# ISL6236A_DEMO.net
KiCad netlist of a schematic drawn in Altium Designer
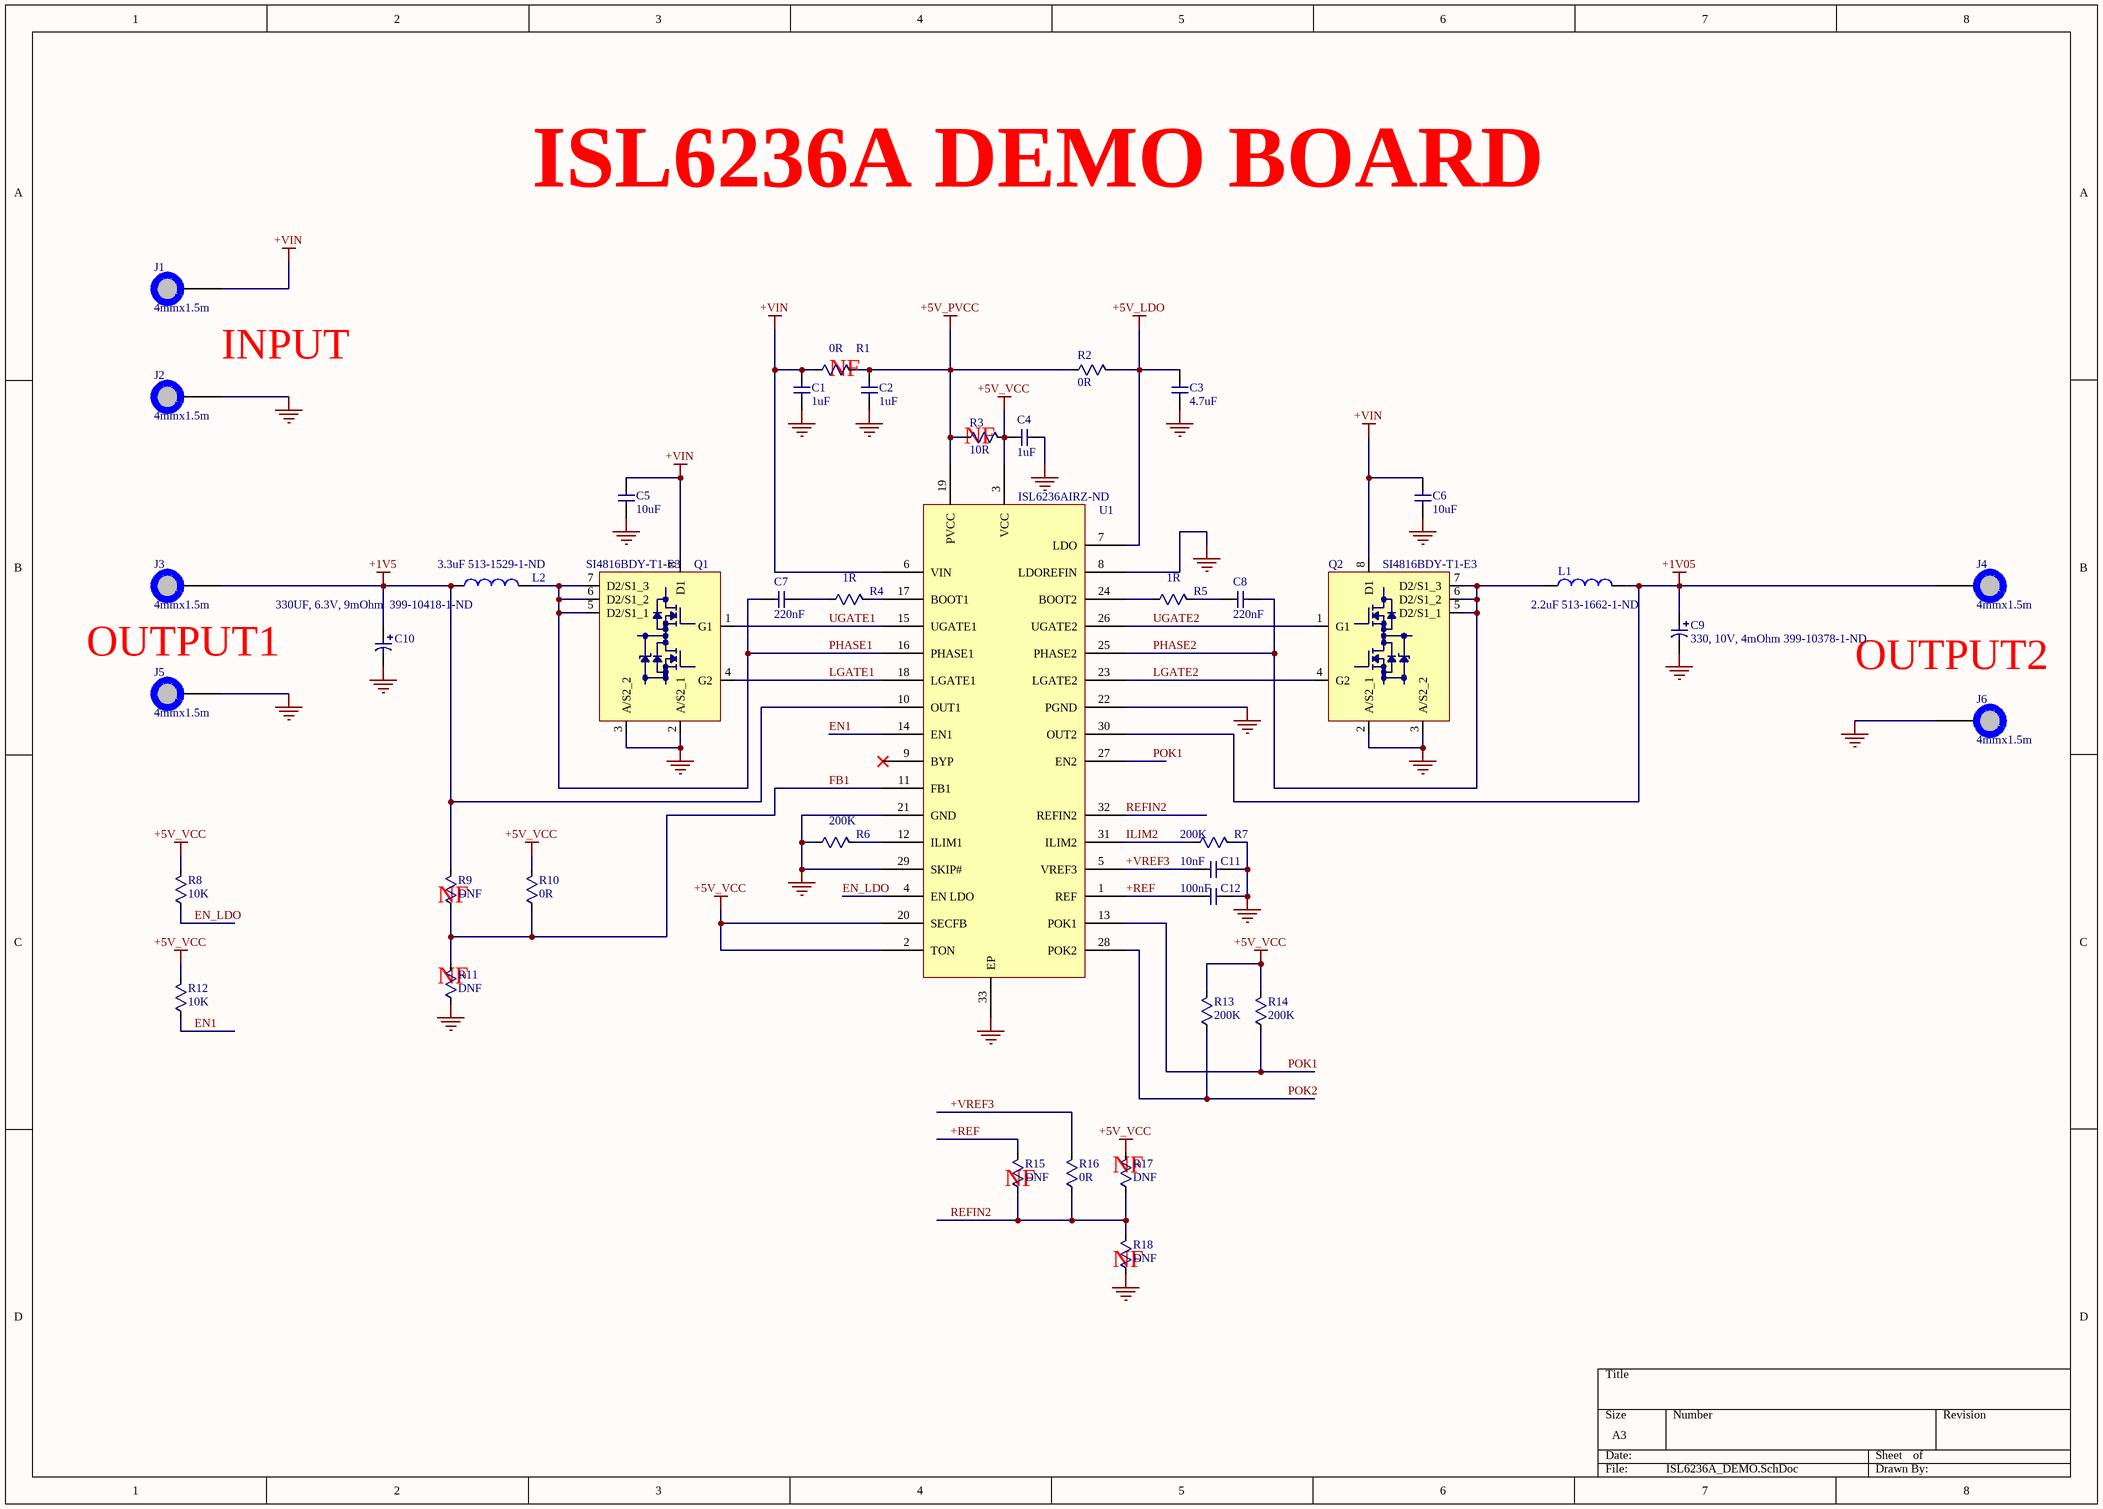
[diagram p0: ISL6236A_DEMO.SchDoc]

(export (version "E")
  (design (tool "Eeschema 10.0.6"))
  (components
    (comp (ref "C1")
      (value "1uF")
      (footprint "C0805")
      (description "CAP CER 1UF 50V 10% X7R 0805")
      (fields
        (field (name "MANUFACTURER") "Samsung Electro-Mechanics America, Inc")
        (field (name "MANUFACTURER PART NUMBER") "CL21B105KBFNNNE")
      )
      (libsource (lib "ISL6236A_DEMO_2") (part "CL21B105KBFNNNE"))
    )
    (comp (ref "C2")
      (value "1uF")
      (footprint "C0805")
      (description "CAP CER 1UF 50V 10% X7R 0805")
      (fields
        (field (name "MANUFACTURER") "Samsung Electro-Mechanics America, Inc")
        (field (name "MANUFACTURER PART NUMBER") "CL21B105KBFNNNE")
      )
      (libsource (lib "ISL6236A_DEMO_2") (part "CL21B105KBFNNNE"))
    )
    (comp (ref "C3")
      (value "4.7uF")
      (footprint "C1206")
      (description "CAP CER 4.7UF 10V 10% X5R 1206")
      (fields
        (field (name "MANUFACTURER") "Samsung Electro-Mechanics America, Inc")
        (field (name "MANUFACTURER PART NUMBER") "CL31A475KPHNNNE")
      )
      (libsource (lib "ISL6236A_DEMO_2") (part "CL31A475KPHNNNE"))
    )
    (comp (ref "C4")
      (value "1uF")
      (footprint "C0805")
      (description "CAP CER 1UF 50V 10% X7R 0805")
      (fields
        (field (name "MANUFACTURER") "Samsung Electro-Mechanics America, Inc")
        (field (name "MANUFACTURER PART NUMBER") "CL21B105KBFNNNE")
      )
      (libsource (lib "ISL6236A_DEMO_2") (part "CL21B105KBFNNNE"))
    )
    (comp (ref "C5")
      (value "10uF")
      (footprint "C1206")
      (description "CAP CER 10UF 50V Y5V 1210")
      (fields
        (field (name "MANUFACTURER") "Murata Electronics North America")
        (field (name "MANUFACTURER PART NUMBER") "GRM32DF51H106ZA01L")
      )
      (libsource (lib "ISL6236A_DEMO_2") (part "GRM32DF51H106ZA01L"))
    )
    (comp (ref "C6")
      (value "10uF")
      (footprint "C1206")
      (description "CAP CER 10UF 50V Y5V 1210")
      (fields
        (field (name "MANUFACTURER") "Murata Electronics North America")
        (field (name "MANUFACTURER PART NUMBER") "GRM32DF51H106ZA01L")
      )
      (libsource (lib "ISL6236A_DEMO_2") (part "GRM32DF51H106ZA01L"))
    )
    (comp (ref "C7")
      (value "220nF")
      (footprint "C0805")
      (description "CAP CER 0.22UF 50V 10% X7R 0805")
      (fields
        (field (name "MANUFACTURER") "Taiyo Yuden")
        (field (name "MANUFACTURER PART NUMBER") "UMK212B7224KG-T")
      )
      (libsource (lib "ISL6236A_DEMO_2") (part "UMK212B7224KG-T"))
    )
    (comp (ref "C8")
      (value "220nF")
      (footprint "C0805")
      (description "CAP CER 0.22UF 50V 10% X7R 0805")
      (fields
        (field (name "MANUFACTURER") "Taiyo Yuden")
        (field (name "MANUFACTURER PART NUMBER") "UMK212B7224KG-T")
      )
      (libsource (lib "ISL6236A_DEMO_2") (part "UMK212B7224KG-T"))
    )
    (comp (ref "C9")
      (value "330, 10V, 4mOhm 399-10378-1-ND")
      (footprint "C7343-43")
      (description "CAP TANT 330UF 10V 20% 2917")
      (fields
        (field (name "MANUFACTURER") "Kemet")
        (field (name "MANUFACTURER PART NUMBER") "T530X337M010ATE004")
      )
      (libsource (lib "ISL6236A_DEMO_2") (part "T530X337M010ATE004"))
    )
    (comp (ref "C10")
      (value "330UF, 6.3V, 9mOhm  399-10418-1-ND")
      (footprint "C7343-31")
      (description "CAP TANT 330UF 6.3V 20% 2917")
      (fields
        (field (name "MANUFACTURER") "Kemet")
        (field (name "MANUFACTURER PART NUMBER") "T520D337M006ATE009")
      )
      (libsource (lib "ISL6236A_DEMO_2") (part "T520D337M006ATE009"))
    )
    (comp (ref "C11")
      (value "10nF")
      (footprint "C0805")
      (description "CAP CER 10000PF 50V 10% X7R 0805")
      (fields
        (field (name "MANUFACTURER") "Kemet")
        (field (name "MANUFACTURER PART NUMBER") "C0805C103K5RACTU")
      )
      (libsource (lib "ISL6236A_DEMO_2") (part "C0805C103K5RACTU"))
    )
    (comp (ref "C12")
      (value "100nF")
      (footprint "C0805")
      (description "CAP CER 0.1UF 50V 10% X7R 0805")
      (fields
        (field (name "MANUFACTURER") "Kemet")
        (field (name "MANUFACTURER PART NUMBER") "C0805C104K5RACTU")
      )
      (libsource (lib "ISL6236A_DEMO_2") (part "C0805C104K5RACTU"))
    )
    (comp (ref "J1")
      (value "4mmx1.5m")
      (footprint "PAD_WITH_HOLE_4MMx1.5MM")
      (description "Pad with hole with 4mmx1.5mm")
      (libsource (lib "ISL6236A_DEMO_2") (part "PAD_WITH_HOLE_4mmx1.5mm"))
    )
    (comp (ref "J2")
      (value "4mmx1.5m")
      (footprint "PAD_WITH_HOLE_4MMx1.5MM")
      (description "Pad with hole with 4mmx1.5mm")
      (libsource (lib "ISL6236A_DEMO_2") (part "PAD_WITH_HOLE_4mmx1.5mm"))
    )
    (comp (ref "J3")
      (value "4mmx1.5m")
      (footprint "PAD_WITH_HOLE_4MMx1.5MM")
      (description "Pad with hole with 4mmx1.5mm")
      (libsource (lib "ISL6236A_DEMO_2") (part "PAD_WITH_HOLE_4mmx1.5mm"))
    )
    (comp (ref "J4")
      (value "4mmx1.5m")
      (footprint "PAD_WITH_HOLE_4MMx1.5MM")
      (description "Pad with hole with 4mmx1.5mm")
      (libsource (lib "ISL6236A_DEMO_2") (part "PAD_WITH_HOLE_4mmx1.5mm"))
    )
    (comp (ref "J5")
      (value "4mmx1.5m")
      (footprint "PAD_WITH_HOLE_4MMx1.5MM")
      (description "Pad with hole with 4mmx1.5mm")
      (libsource (lib "ISL6236A_DEMO_2") (part "PAD_WITH_HOLE_4mmx1.5mm"))
    )
    (comp (ref "J6")
      (value "4mmx1.5m")
      (footprint "PAD_WITH_HOLE_4MMx1.5MM")
      (description "Pad with hole with 4mmx1.5mm")
      (libsource (lib "ISL6236A_DEMO_2") (part "PAD_WITH_HOLE_4mmx1.5mm"))
    )
    (comp (ref "L1")
      (value "2.2uF 513-1662-1-ND")
      (footprint "DR125")
      (description "FIXED IND 2.2UH 10.9A 4.5 MOHM")
      (fields
        (field (name "MANUFACTURER") "Eaton Bussmann")
        (field (name "MANUFACTURER PART NUMBER") "DR125-2R2-R")
      )
      (libsource (lib "ISL6236A_DEMO_2") (part "DR125-2R2-R"))
    )
    (comp (ref "L2")
      (value "3.3uF 513-1529-1-ND")
      (footprint "DR125")
      (description "FIXED IND 3.3UH 9.26A 6.3 MOHM")
      (fields
        (field (name "MANUFACTURER") "Eaton Bussmann")
        (field (name "MANUFACTURER PART NUMBER") "DR125-3R3-R")
      )
      (libsource (lib "ISL6236A_DEMO_2") (part "DR125-3R3-R"))
    )
    (comp (ref "Q1")
      (value "SI4816BDY-T1-E3")
      (footprint "SO-8")
      (description "MOSFET 2N-CH 30V 5.8A 8-SOIC")
      (fields (field (name "MANUFACTURER") "Vishay Siliconix"))
      (libsource (lib "ISL6236A_DEMO_2") (part "SI4816BDY-T1-E3"))
    )
    (comp (ref "Q2")
      (value "SI4816BDY-T1-E3")
      (footprint "SO-8")
      (description "MOSFET 2N-CH 30V 5.8A 8-SOIC")
      (fields (field (name "MANUFACTURER") "Vishay Siliconix"))
      (libsource (lib "ISL6236A_DEMO_2") (part "SI4816BDY-T1-E3"))
    )
    (comp (ref "R1")
      (value "0R")
      (footprint "R0805")
      (description "RES 0.0 OHM 1/8W JUMP 0805 SMD")
      (fields
        (field (name "MANUFACTURER") "Panasonic Electronic Components")
        (field (name "MANUFACTURER PART NUMBER") "ERJ-6GEY0R00V")
      )
      (libsource (lib "ISL6236A_DEMO_2") (part "ERJ-6GEY0R00V"))
    )
    (comp (ref "R2")
      (value "0R")
      (footprint "R0805")
      (description "RES 0.0 OHM 1/8W JUMP 0805 SMD")
      (fields
        (field (name "MANUFACTURER") "Panasonic Electronic Components")
        (field (name "MANUFACTURER PART NUMBER") "ERJ-6GEY0R00V")
      )
      (libsource (lib "ISL6236A_DEMO_2") (part "ERJ-6GEY0R00V"))
    )
    (comp (ref "R3")
      (value "10R")
      (footprint "R0805")
      (description "RES 10 OHM 1/8W 1% 0805 SMD")
      (fields
        (field (name "MANUFACTURER") "Panasonic Electronic Components")
        (field (name "MANUFACTURER PART NUMBER") "ERJ-6ENF10R0V")
      )
      (libsource (lib "ISL6236A_DEMO_2") (part "ERJ-6ENF10R0V"))
    )
    (comp (ref "R4")
      (value "1R")
      (footprint "R0805")
      (description "RES 1 OHM 1/8W 1% 0805 SMD")
      (fields
        (field (name "MANUFACTURER") "Panasonic Electronic Components")
        (field (name "MANUFACTURER PART NUMBER") "ERJ-6RQF1R0V")
      )
      (libsource (lib "ISL6236A_DEMO_2") (part "ERJ-6RQF1R0V"))
    )
    (comp (ref "R5")
      (value "1R")
      (footprint "R0805")
      (description "RES 1 OHM 1/8W 1% 0805 SMD")
      (fields
        (field (name "MANUFACTURER") "Panasonic Electronic Components")
        (field (name "MANUFACTURER PART NUMBER") "ERJ-6RQF1R0V")
      )
      (libsource (lib "ISL6236A_DEMO_2") (part "ERJ-6RQF1R0V"))
    )
    (comp (ref "R6")
      (value "200K")
      (footprint "R0805")
      (description "RES 200K OHM 1/8W 1% 0805")
      (fields
        (field (name "MANUFACTURER") "Stackpole Electronics Inc")
        (field (name "MANUFACTURER PART NUMBER") "RMCF0805FT200K")
      )
      (libsource (lib "ISL6236A_DEMO_2") (part "RMCF0805FT200K"))
    )
    (comp (ref "R7")
      (value "200K")
      (footprint "R0805")
      (description "RES 200K OHM 1/8W 1% 0805")
      (fields
        (field (name "MANUFACTURER") "Stackpole Electronics Inc")
        (field (name "MANUFACTURER PART NUMBER") "RMCF0805FT200K")
      )
      (libsource (lib "ISL6236A_DEMO_2") (part "RMCF0805FT200K"))
    )
    (comp (ref "R8")
      (value "10K")
      (footprint "R0805")
      (description "RES 10K OHM 1/8W 5% 0805 SMD")
      (fields
        (field (name "MANUFACTURER") "Panasonic Electronic Components")
        (field (name "MANUFACTURER PART NUMBER") "ERJ-6GEYJ103V")
      )
      (libsource (lib "ISL6236A_DEMO_2") (part "ERJ-6GEYJ103V"))
    )
    (comp (ref "R9") (value "DNF") (footprint "R0805") (libsource (lib "ISL6236A_DEMO_2") (part "RES")))
    (comp (ref "R10")
      (value "0R")
      (footprint "R0805")
      (description "RES 0.0 OHM 1/8W JUMP 0805 SMD")
      (fields
        (field (name "MANUFACTURER") "Panasonic Electronic Components")
        (field (name "MANUFACTURER PART NUMBER") "ERJ-6GEY0R00V")
      )
      (libsource (lib "ISL6236A_DEMO_2") (part "ERJ-6GEY0R00V"))
    )
    (comp (ref "R11") (value "DNF") (footprint "R0805") (libsource (lib "ISL6236A_DEMO_2") (part "RES")))
    (comp (ref "R12")
      (value "10K")
      (footprint "R0805")
      (description "RES 10K OHM 1/8W 5% 0805 SMD")
      (fields
        (field (name "MANUFACTURER") "Panasonic Electronic Components")
        (field (name "MANUFACTURER PART NUMBER") "ERJ-6GEYJ103V")
      )
      (libsource (lib "ISL6236A_DEMO_2") (part "ERJ-6GEYJ103V"))
    )
    (comp (ref "R13")
      (value "200K")
      (footprint "R0805")
      (description "RES 200K OHM 1/8W 1% 0805")
      (fields
        (field (name "MANUFACTURER") "Stackpole Electronics Inc")
        (field (name "MANUFACTURER PART NUMBER") "RMCF0805FT200K")
      )
      (libsource (lib "ISL6236A_DEMO_2") (part "RMCF0805FT200K"))
    )
    (comp (ref "R14")
      (value "200K")
      (footprint "R0805")
      (description "RES 200K OHM 1/8W 1% 0805")
      (fields
        (field (name "MANUFACTURER") "Stackpole Electronics Inc")
        (field (name "MANUFACTURER PART NUMBER") "RMCF0805FT200K")
      )
      (libsource (lib "ISL6236A_DEMO_2") (part "RMCF0805FT200K"))
    )
    (comp (ref "R15") (value "DNF") (footprint "R0805") (libsource (lib "ISL6236A_DEMO_2") (part "RES")))
    (comp (ref "R16")
      (value "0R")
      (footprint "R0805")
      (description "RES 0.0 OHM 1/8W JUMP 0805 SMD")
      (fields
        (field (name "MANUFACTURER") "Panasonic Electronic Components")
        (field (name "MANUFACTURER PART NUMBER") "ERJ-6GEY0R00V")
      )
      (libsource (lib "ISL6236A_DEMO_2") (part "ERJ-6GEY0R00V"))
    )
    (comp (ref "R17") (value "DNF") (footprint "R0805") (libsource (lib "ISL6236A_DEMO_2") (part "RES")))
    (comp (ref "R18") (value "DNF") (footprint "R0805") (libsource (lib "ISL6236A_DEMO_2") (part "RES")))
    (comp (ref "U1")
      (value "ISL6236AIRZ-ND")
      (footprint "L32.5x5B")
      (description "IC MAIN PWR CTRLR QUAD 32-QFN")
      (fields
        (field (name "MANUFACTURER") "Intersil")
        (field (name "MANUFACTURER PART NUMBER") "ISL6236AIRZ")
      )
      (libsource (lib "ISL6236A_DEMO_2") (part "ISL6236AIRZ"))
    )
  )
  (nets
    (net (code "1") (name "+1V05") (class "Default")
      (node (ref "C9") (pin "1") (pinfunction "1_1") (pintype "passive"))
      (node (ref "J4") (pin "1") (pinfunction "1_1") (pintype "passive"))
      (node (ref "L1") (pin "2") (pinfunction "2_2") (pintype "passive"))
      (node (ref "U1") (pin "30") (pinfunction "OUT2_30") (pintype "passive"))
    )
    (net (code "2") (name "+1V5") (class "Default")
      (node (ref "C10") (pin "1") (pinfunction "1_1") (pintype "passive"))
      (node (ref "J3") (pin "1") (pinfunction "1_1") (pintype "passive"))
      (node (ref "L2") (pin "1") (pinfunction "1_1") (pintype "passive"))
      (node (ref "R9") (pin "2") (pinfunction "2_2") (pintype "passive"))
      (node (ref "U1") (pin "10") (pinfunction "OUT1_10") (pintype "passive"))
    )
    (net (code "3") (name "+5V_LDO") (class "Default")
      (node (ref "C3") (pin "2") (pinfunction "2_2") (pintype "passive"))
      (node (ref "R2") (pin "2") (pinfunction "2_2") (pintype "passive"))
      (node (ref "U1") (pin "7") (pinfunction "LDO_7") (pintype "passive"))
    )
    (net (code "4") (name "+5V_PVCC") (class "Default")
      (node (ref "C2") (pin "2") (pinfunction "2_2") (pintype "passive"))
      (node (ref "R1") (pin "2") (pinfunction "2_2") (pintype "passive"))
      (node (ref "R2") (pin "1") (pinfunction "1_1") (pintype "passive"))
      (node (ref "R3") (pin "1") (pinfunction "1_1") (pintype "passive"))
      (node (ref "U1") (pin "19") (pinfunction "PVCC_19") (pintype "passive"))
    )
    (net (code "5") (name "+5V_VCC") (class "Default")
      (node (ref "C4") (pin "1") (pinfunction "1_1") (pintype "passive"))
      (node (ref "R10") (pin "2") (pinfunction "2_2") (pintype "passive"))
      (node (ref "R12") (pin "2") (pinfunction "2_2") (pintype "passive"))
      (node (ref "R13") (pin "2") (pinfunction "2_2") (pintype "passive"))
      (node (ref "R14") (pin "2") (pinfunction "2_2") (pintype "passive"))
      (node (ref "R17") (pin "2") (pinfunction "2_2") (pintype "passive"))
      (node (ref "R3") (pin "2") (pinfunction "2_2") (pintype "passive"))
      (node (ref "R8") (pin "2") (pinfunction "2_2") (pintype "passive"))
      (node (ref "U1") (pin "2") (pinfunction "TON_2") (pintype "passive"))
      (node (ref "U1") (pin "20") (pinfunction "SECFB_20") (pintype "passive"))
      (node (ref "U1") (pin "3") (pinfunction "VCC_3") (pintype "passive"))
    )
    (net (code "6") (name "+VIN") (class "Default")
      (node (ref "C1") (pin "2") (pinfunction "2_2") (pintype "passive"))
      (node (ref "C5") (pin "2") (pinfunction "2_2") (pintype "passive"))
      (node (ref "C6") (pin "2") (pinfunction "2_2") (pintype "passive"))
      (node (ref "J1") (pin "1") (pinfunction "1_1") (pintype "passive"))
      (node (ref "Q1") (pin "8") (pinfunction "D1_8") (pintype "passive"))
      (node (ref "Q2") (pin "8") (pinfunction "D1_8") (pintype "passive"))
      (node (ref "R1") (pin "1") (pinfunction "1_1") (pintype "passive"))
      (node (ref "U1") (pin "6") (pinfunction "VIN_6") (pintype "passive"))
    )
    (net (code "7") (name "/+REF") (class "Default")
      (node (ref "C12") (pin "1") (pinfunction "1_1") (pintype "passive"))
      (node (ref "R15") (pin "2") (pinfunction "2_2") (pintype "passive"))
      (node (ref "U1") (pin "1") (pinfunction "REF_1") (pintype "passive"))
    )
    (net (code "8") (name "/+VREF3") (class "Default")
      (node (ref "C11") (pin "1") (pinfunction "1_1") (pintype "passive"))
      (node (ref "R16") (pin "2") (pinfunction "2_2") (pintype "passive"))
      (node (ref "U1") (pin "5") (pinfunction "VREF3_5") (pintype "passive"))
    )
    (net (code "9") (name "/EN1") (class "Default")
      (node (ref "R12") (pin "1") (pinfunction "1_1") (pintype "passive"))
      (node (ref "U1") (pin "14") (pinfunction "EN1_14") (pintype "passive"))
    )
    (net (code "10") (name "/EN_LDO") (class "Default")
      (node (ref "R8") (pin "1") (pinfunction "1_1") (pintype "passive"))
      (node (ref "U1") (pin "4") (pinfunction "EN_LDO_4") (pintype "passive"))
    )
    (net (code "11") (name "/FB1") (class "Default")
      (node (ref "R10") (pin "1") (pinfunction "1_1") (pintype "passive"))
      (node (ref "R11") (pin "2") (pinfunction "2_2") (pintype "passive"))
      (node (ref "R9") (pin "1") (pinfunction "1_1") (pintype "passive"))
      (node (ref "U1") (pin "11") (pinfunction "FB1_11") (pintype "passive"))
    )
    (net (code "12") (name "/ILIM2") (class "Default")
      (node (ref "R7") (pin "1") (pinfunction "1_1") (pintype "passive"))
      (node (ref "U1") (pin "31") (pinfunction "ILIM2_31") (pintype "passive"))
    )
    (net (code "13") (name "/LGATE1") (class "Default")
      (node (ref "Q1") (pin "4") (pinfunction "G2_4") (pintype "passive"))
      (node (ref "U1") (pin "18") (pinfunction "LGATE1_18") (pintype "passive"))
    )
    (net (code "14") (name "/LGATE2") (class "Default")
      (node (ref "Q2") (pin "4") (pinfunction "G2_4") (pintype "passive"))
      (node (ref "U1") (pin "23") (pinfunction "LGATE2_23") (pintype "passive"))
    )
    (net (code "15") (name "/PHASE1") (class "Default")
      (node (ref "C7") (pin "1") (pinfunction "1_1") (pintype "passive"))
      (node (ref "L2") (pin "2") (pinfunction "2_2") (pintype "passive"))
      (node (ref "Q1") (pin "5") (pinfunction "D2/S1_1_5") (pintype "passive"))
      (node (ref "Q1") (pin "6") (pinfunction "D2/S1_2_6") (pintype "passive"))
      (node (ref "Q1") (pin "7") (pinfunction "D2/S1_3_7") (pintype "passive"))
      (node (ref "U1") (pin "16") (pinfunction "PHASE1_16") (pintype "passive"))
    )
    (net (code "16") (name "/PHASE2") (class "Default")
      (node (ref "C8") (pin "2") (pinfunction "2_2") (pintype "passive"))
      (node (ref "L1") (pin "1") (pinfunction "1_1") (pintype "passive"))
      (node (ref "Q2") (pin "5") (pinfunction "D2/S1_1_5") (pintype "passive"))
      (node (ref "Q2") (pin "6") (pinfunction "D2/S1_2_6") (pintype "passive"))
      (node (ref "Q2") (pin "7") (pinfunction "D2/S1_3_7") (pintype "passive"))
      (node (ref "U1") (pin "25") (pinfunction "PHASE2_25") (pintype "passive"))
    )
    (net (code "17") (name "/POK1") (class "Default")
      (node (ref "R14") (pin "1") (pinfunction "1_1") (pintype "passive"))
      (node (ref "U1") (pin "13") (pinfunction "POK1_13") (pintype "passive"))
      (node (ref "U1") (pin "27") (pinfunction "EN2_27") (pintype "passive"))
    )
    (net (code "18") (name "/POK2") (class "Default")
      (node (ref "R13") (pin "1") (pinfunction "1_1") (pintype "passive"))
      (node (ref "U1") (pin "28") (pinfunction "POK2_28") (pintype "passive"))
    )
    (net (code "19") (name "/REFIN2") (class "Default")
      (node (ref "R15") (pin "1") (pinfunction "1_1") (pintype "passive"))
      (node (ref "R16") (pin "1") (pinfunction "1_1") (pintype "passive"))
      (node (ref "R17") (pin "1") (pinfunction "1_1") (pintype "passive"))
      (node (ref "R18") (pin "2") (pinfunction "2_2") (pintype "passive"))
      (node (ref "U1") (pin "32") (pinfunction "REFIN2_32") (pintype "passive"))
    )
    (net (code "20") (name "/UGATE1") (class "Default")
      (node (ref "Q1") (pin "1") (pinfunction "G1_1") (pintype "passive"))
      (node (ref "U1") (pin "15") (pinfunction "UGATE1_15") (pintype "passive"))
    )
    (net (code "21") (name "/UGATE2") (class "Default")
      (node (ref "Q2") (pin "1") (pinfunction "G1_1") (pintype "passive"))
      (node (ref "U1") (pin "26") (pinfunction "UGATE2_26") (pintype "passive"))
    )
    (net (code "22") (name "GND") (class "Default")
      (node (ref "C1") (pin "1") (pinfunction "1_1") (pintype "passive"))
      (node (ref "C10") (pin "2") (pinfunction "2_2") (pintype "passive"))
      (node (ref "C11") (pin "2") (pinfunction "2_2") (pintype "passive"))
      (node (ref "C12") (pin "2") (pinfunction "2_2") (pintype "passive"))
      (node (ref "C2") (pin "1") (pinfunction "1_1") (pintype "passive"))
      (node (ref "C3") (pin "1") (pinfunction "1_1") (pintype "passive"))
      (node (ref "C4") (pin "2") (pinfunction "2_2") (pintype "passive"))
      (node (ref "C5") (pin "1") (pinfunction "1_1") (pintype "passive"))
      (node (ref "C6") (pin "1") (pinfunction "1_1") (pintype "passive"))
      (node (ref "C9") (pin "2") (pinfunction "2_2") (pintype "passive"))
      (node (ref "J2") (pin "1") (pinfunction "1_1") (pintype "passive"))
      (node (ref "J5") (pin "1") (pinfunction "1_1") (pintype "passive"))
      (node (ref "J6") (pin "1") (pinfunction "1_1") (pintype "passive"))
      (node (ref "Q1") (pin "2") (pinfunction "A/S2_1_2") (pintype "passive"))
      (node (ref "Q1") (pin "3") (pinfunction "A/S2_2_3") (pintype "passive"))
      (node (ref "Q2") (pin "2") (pinfunction "A/S2_1_2") (pintype "passive"))
      (node (ref "Q2") (pin "3") (pinfunction "A/S2_2_3") (pintype "passive"))
      (node (ref "R11") (pin "1") (pinfunction "1_1") (pintype "passive"))
      (node (ref "R18") (pin "1") (pinfunction "1_1") (pintype "passive"))
      (node (ref "R6") (pin "1") (pinfunction "1_1") (pintype "passive"))
      (node (ref "R7") (pin "2") (pinfunction "2_2") (pintype "passive"))
      (node (ref "U1") (pin "21") (pinfunction "GND_21") (pintype "passive"))
      (node (ref "U1") (pin "22") (pinfunction "PGND_22") (pintype "passive"))
      (node (ref "U1") (pin "29") (pinfunction "SKIP#_29") (pintype "passive"))
      (node (ref "U1") (pin "33") (pinfunction "EP_33") (pintype "passive"))
      (node (ref "U1") (pin "8") (pinfunction "LDOREFIN_8") (pintype "passive"))
    )
    (net (code "23") (name "Net-(C7-Pad2)") (class "Default")
      (node (ref "C7") (pin "2") (pinfunction "2_2") (pintype "passive"))
      (node (ref "R4") (pin "1") (pinfunction "1_1") (pintype "passive"))
    )
    (net (code "24") (name "Net-(C8-Pad1)") (class "Default")
      (node (ref "C8") (pin "1") (pinfunction "1_1") (pintype "passive"))
      (node (ref "R5") (pin "2") (pinfunction "2_2") (pintype "passive"))
    )
    (net (code "25") (name "Net-(U1-BOOT1)") (class "Default")
      (node (ref "R4") (pin "2") (pinfunction "2_2") (pintype "passive"))
      (node (ref "U1") (pin "17") (pinfunction "BOOT1_17") (pintype "passive"))
    )
    (net (code "26") (name "Net-(U1-BOOT2)") (class "Default")
      (node (ref "R5") (pin "1") (pinfunction "1_1") (pintype "passive"))
      (node (ref "U1") (pin "24") (pinfunction "BOOT2_24") (pintype "passive"))
    )
    (net (code "27") (name "Net-(U1-ILIM1)") (class "Default")
      (node (ref "R6") (pin "2") (pinfunction "2_2") (pintype "passive"))
      (node (ref "U1") (pin "12") (pinfunction "ILIM1_12") (pintype "passive"))
    )
    (net (code "28") (name "unconnected-(U1-BYP-Pad9)") (class "Default")
      (node (ref "U1") (pin "9") (pinfunction "BYP_9") (pintype "passive+no_connect"))
    )
  )
)
